# MCU.net
KiCad netlist of a schematic drawn in Altium Designer
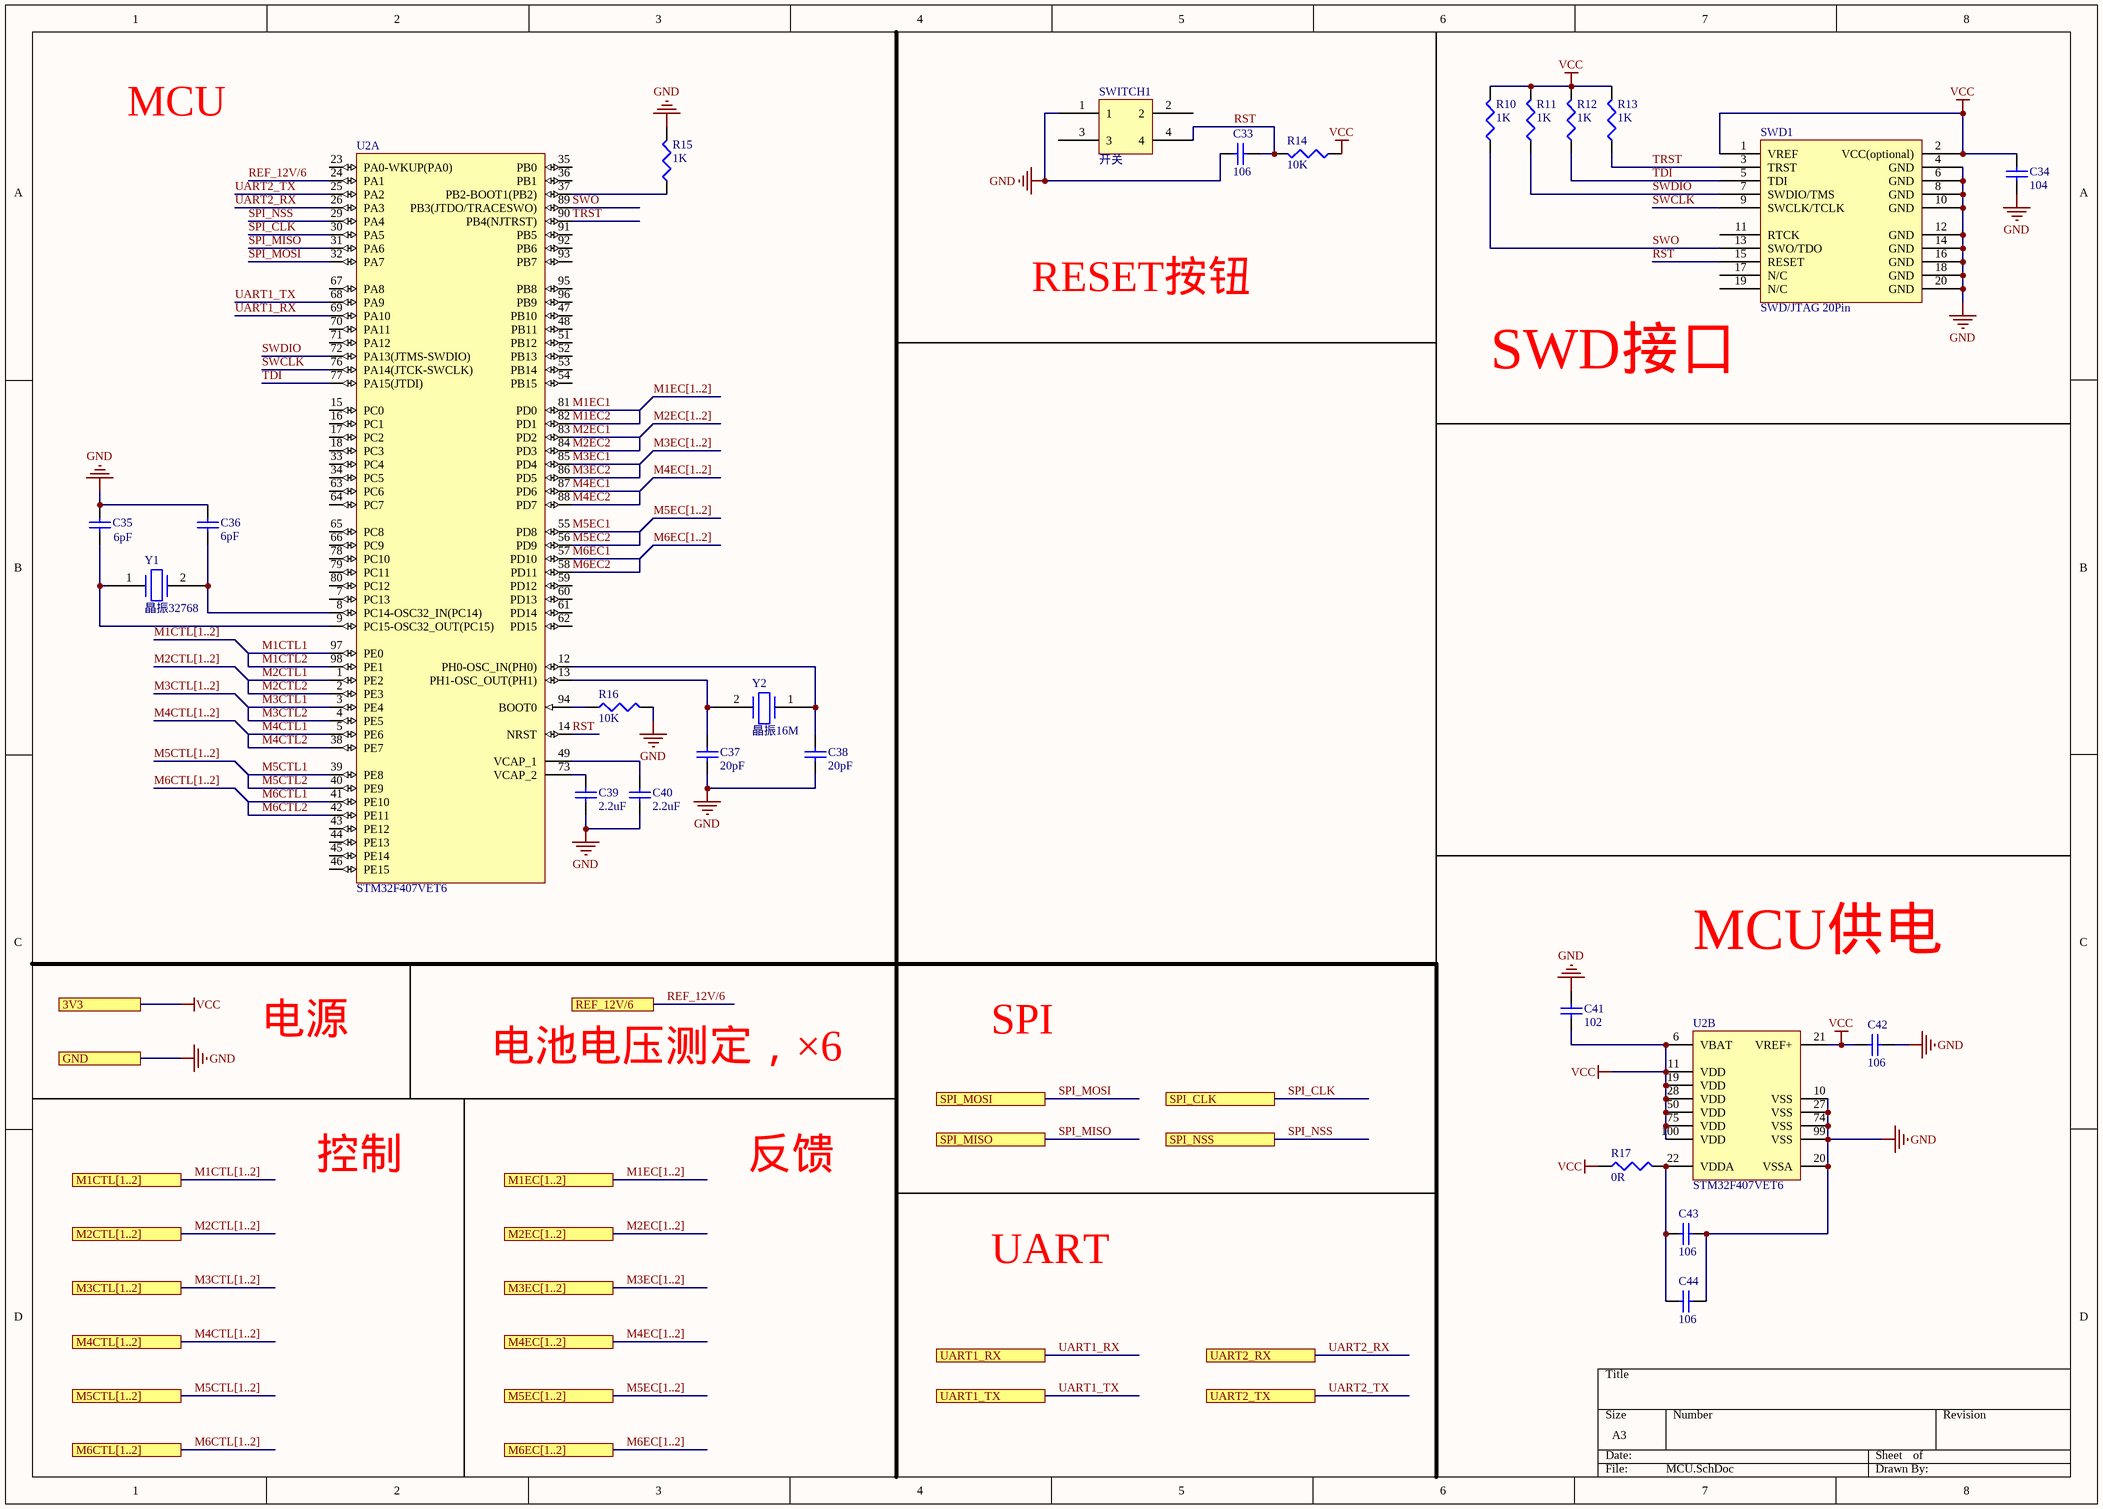
[diagram p0: MCU.SchDoc]

(export (version "E")
  (design (tool "Eeschema 10.0.6"))
  (components
    (comp (ref "C33")
      (value "106")
      (footprint "MY0805")
      (description "Capacitor")
      (fields (field (name "PUBLISHER") "Altium Limited"))
      (libsource (lib "Miscellaneous Devices") (part "Cap"))
    )
    (comp (ref "C34")
      (value "104")
      (footprint "MY0805")
      (description "Capacitor")
      (fields (field (name "PUBLISHER") "Altium Limited"))
      (libsource (lib "Miscellaneous Devices") (part "Cap"))
    )
    (comp (ref "C35")
      (value "6pF")
      (footprint "MY0805")
      (description "Capacitor")
      (fields (field (name "PUBLISHER") "Altium Limited"))
      (libsource (lib "Miscellaneous Devices") (part "Cap"))
    )
    (comp (ref "C36")
      (value "6pF")
      (footprint "MY0805")
      (description "Capacitor")
      (fields (field (name "PUBLISHER") "Altium Limited"))
      (libsource (lib "Miscellaneous Devices") (part "Cap"))
    )
    (comp (ref "C37")
      (value "20pF")
      (footprint "MY0805")
      (description "Capacitor")
      (fields (field (name "PUBLISHER") "Altium Limited"))
      (libsource (lib "Miscellaneous Devices") (part "Cap"))
    )
    (comp (ref "C38")
      (value "20pF")
      (footprint "MY0805")
      (description "Capacitor")
      (fields (field (name "PUBLISHER") "Altium Limited"))
      (libsource (lib "Miscellaneous Devices") (part "Cap"))
    )
    (comp (ref "C39")
      (value "2.2uF")
      (footprint "MY0805")
      (description "Capacitor")
      (fields (field (name "PUBLISHER") "Altium Limited"))
      (libsource (lib "Miscellaneous Devices") (part "Cap"))
    )
    (comp (ref "C40")
      (value "2.2uF")
      (footprint "MY0805")
      (description "Capacitor")
      (fields (field (name "PUBLISHER") "Altium Limited"))
      (libsource (lib "Miscellaneous Devices") (part "Cap"))
    )
    (comp (ref "C41")
      (value "102")
      (footprint "MY0805")
      (description "Capacitor")
      (fields (field (name "PUBLISHER") "Altium Limited"))
      (libsource (lib "Miscellaneous Devices") (part "Cap"))
    )
    (comp (ref "C42")
      (value "106")
      (footprint "MY0805")
      (description "Capacitor")
      (fields (field (name "PUBLISHER") "Altium Limited"))
      (libsource (lib "Miscellaneous Devices") (part "Cap"))
    )
    (comp (ref "C43")
      (value "106")
      (footprint "MY0805")
      (description "Capacitor")
      (fields (field (name "PUBLISHER") "Altium Limited"))
      (libsource (lib "Miscellaneous Devices") (part "Cap"))
    )
    (comp (ref "C44")
      (value "106")
      (footprint "MY0805")
      (description "Capacitor")
      (fields (field (name "PUBLISHER") "Altium Limited"))
      (libsource (lib "Miscellaneous Devices") (part "Cap"))
    )
    (comp (ref "R10")
      (value "1K")
      (footprint "MY0805")
      (description "Resistor")
      (fields (field (name "PUBLISHER") "Altium Limited"))
      (libsource (lib "Miscellaneous Devices") (part "Res3"))
    )
    (comp (ref "R11")
      (value "1K")
      (footprint "MY0805")
      (description "Resistor")
      (fields (field (name "PUBLISHER") "Altium Limited"))
      (libsource (lib "Miscellaneous Devices") (part "Res3"))
    )
    (comp (ref "R12")
      (value "1K")
      (footprint "MY0805")
      (description "Resistor")
      (fields (field (name "PUBLISHER") "Altium Limited"))
      (libsource (lib "Miscellaneous Devices") (part "Res3"))
    )
    (comp (ref "R13")
      (value "1K")
      (footprint "MY0805")
      (description "Resistor")
      (fields (field (name "PUBLISHER") "Altium Limited"))
      (libsource (lib "Miscellaneous Devices") (part "Res3"))
    )
    (comp (ref "R14")
      (value "10K")
      (footprint "MY0805")
      (description "Resistor")
      (fields (field (name "PUBLISHER") "Altium Limited"))
      (libsource (lib "Miscellaneous Devices") (part "Res3"))
    )
    (comp (ref "R15")
      (value "1K")
      (footprint "MY0805")
      (description "Resistor")
      (fields (field (name "PUBLISHER") "Altium Limited"))
      (libsource (lib "Miscellaneous Devices") (part "Res3"))
    )
    (comp (ref "R16")
      (value "10K")
      (footprint "MY0805")
      (description "Resistor")
      (fields (field (name "PUBLISHER") "Altium Limited"))
      (libsource (lib "Miscellaneous Devices") (part "Res3"))
    )
    (comp (ref "R17")
      (value "0R")
      (footprint "MY0805")
      (description "Resistor")
      (fields (field (name "PUBLISHER") "Altium Limited"))
      (libsource (lib "Miscellaneous Devices") (part "Res3"))
    )
    (comp (ref "SWD1")
      (value "SWD/JTAG 20Pin")
      (footprint "SWD 20Pin")
      (libsource (lib "Schlib1") (part "SWD/JTAG 20Pin"))
    )
    (comp (ref "SWITCH1") (value "开关") (footprint "开关") (libsource (lib "Schlib1") (part "开关")))
    (comp (ref "U2")
      (value "STM32F407VET6")
      (footprint "STM-LQFP100_N")
      (fields (field (name "MANUFACTURER") "STMicroelectronics"))
      (libsource (lib "STMicroelectronics STM32 F4") (part "STM32F407VET6"))
    )
    (comp (ref "Y1") (value "晶振32768") (footprint "晶振32768K_AT38") (libsource (lib "Schlib1") (part "晶振")))
    (comp (ref "Y2") (value "晶振16M") (footprint "晶振16M") (libsource (lib "Schlib1") (part "晶振")))
  )
  (nets
    (net (code "1") (name "/M1CTL1") (class "Default")
      (node (ref "U2") (pin "97") (pinfunction "PE0_97") (pintype "bidirectional"))
    )
    (net (code "2") (name "/M1CTL2") (class "Default")
      (node (ref "U2") (pin "98") (pinfunction "PE1_98") (pintype "bidirectional"))
    )
    (net (code "4") (name "/M1EC1") (class "Default")
      (node (ref "U2") (pin "81") (pinfunction "PD0_81") (pintype "bidirectional"))
    )
    (net (code "5") (name "/M1EC2") (class "Default")
      (node (ref "U2") (pin "82") (pinfunction "PD1_82") (pintype "bidirectional"))
    )
    (net (code "7") (name "/M2CTL1") (class "Default")
      (node (ref "U2") (pin "1") (pinfunction "PE2_1") (pintype "bidirectional"))
    )
    (net (code "8") (name "/M2CTL2") (class "Default")
      (node (ref "U2") (pin "2") (pinfunction "PE3_2") (pintype "bidirectional"))
    )
    (net (code "10") (name "/M2EC1") (class "Default")
      (node (ref "U2") (pin "83") (pinfunction "PD2_83") (pintype "bidirectional"))
    )
    (net (code "11") (name "/M2EC2") (class "Default")
      (node (ref "U2") (pin "84") (pinfunction "PD3_84") (pintype "bidirectional"))
    )
    (net (code "13") (name "/M3CTL1") (class "Default")
      (node (ref "U2") (pin "3") (pinfunction "PE4_3") (pintype "bidirectional"))
    )
    (net (code "14") (name "/M3CTL2") (class "Default")
      (node (ref "U2") (pin "4") (pinfunction "PE5_4") (pintype "bidirectional"))
    )
    (net (code "16") (name "/M3EC1") (class "Default")
      (node (ref "U2") (pin "85") (pinfunction "PD4_85") (pintype "bidirectional"))
    )
    (net (code "17") (name "/M3EC2") (class "Default")
      (node (ref "U2") (pin "86") (pinfunction "PD5_86") (pintype "bidirectional"))
    )
    (net (code "19") (name "/M4CTL1") (class "Default")
      (node (ref "U2") (pin "5") (pinfunction "PE6_5") (pintype "bidirectional"))
    )
    (net (code "20") (name "/M4CTL2") (class "Default")
      (node (ref "U2") (pin "38") (pinfunction "PE7_38") (pintype "bidirectional"))
    )
    (net (code "22") (name "/M4EC1") (class "Default")
      (node (ref "U2") (pin "87") (pinfunction "PD6_87") (pintype "bidirectional"))
    )
    (net (code "23") (name "/M4EC2") (class "Default")
      (node (ref "U2") (pin "88") (pinfunction "PD7_88") (pintype "bidirectional"))
    )
    (net (code "25") (name "/M5CTL1") (class "Default")
      (node (ref "U2") (pin "39") (pinfunction "PE8_39") (pintype "bidirectional"))
    )
    (net (code "26") (name "/M5CTL2") (class "Default")
      (node (ref "U2") (pin "40") (pinfunction "PE9_40") (pintype "bidirectional"))
    )
    (net (code "28") (name "/M5EC1") (class "Default")
      (node (ref "U2") (pin "55") (pinfunction "PD8_55") (pintype "bidirectional"))
    )
    (net (code "29") (name "/M5EC2") (class "Default")
      (node (ref "U2") (pin "56") (pinfunction "PD9_56") (pintype "bidirectional"))
    )
    (net (code "31") (name "/M6CTL1") (class "Default")
      (node (ref "U2") (pin "41") (pinfunction "PE10_41") (pintype "bidirectional"))
    )
    (net (code "32") (name "/M6CTL2") (class "Default")
      (node (ref "U2") (pin "42") (pinfunction "PE11_42") (pintype "bidirectional"))
    )
    (net (code "34") (name "/M6EC1") (class "Default")
      (node (ref "U2") (pin "57") (pinfunction "PD10_57") (pintype "bidirectional"))
    )
    (net (code "35") (name "/M6EC2") (class "Default")
      (node (ref "U2") (pin "58") (pinfunction "PD11_58") (pintype "bidirectional"))
    )
    (net (code "37") (name "/REF_12V{slash}6") (class "Default")
      (node (ref "U2") (pin "24") (pinfunction "PA1_24") (pintype "bidirectional"))
    )
    (net (code "38") (name "/RST") (class "Default")
      (node (ref "C33") (pin "2") (pinfunction "2_2") (pintype "passive"))
      (node (ref "R14") (pin "2") (pinfunction "2_2") (pintype "passive"))
      (node (ref "SWD1") (pin "15") (pinfunction "RESET_15") (pintype "passive"))
      (node (ref "SWITCH1") (pin "4") (pinfunction "4_4") (pintype "passive"))
      (node (ref "U2") (pin "14") (pinfunction "NRST_14") (pintype "bidirectional"))
    )
    (net (code "39") (name "/SPI_CLK") (class "Default")
      (node (ref "U2") (pin "30") (pinfunction "PA5_30") (pintype "bidirectional"))
    )
    (net (code "40") (name "/SPI_MISO") (class "Default")
      (node (ref "U2") (pin "31") (pinfunction "PA6_31") (pintype "bidirectional"))
    )
    (net (code "41") (name "/SPI_MOSI") (class "Default")
      (node (ref "U2") (pin "32") (pinfunction "PA7_32") (pintype "bidirectional"))
    )
    (net (code "42") (name "/SPI_NSS") (class "Default")
      (node (ref "U2") (pin "29") (pinfunction "PA4_29") (pintype "bidirectional"))
    )
    (net (code "43") (name "/SWCLK") (class "Default")
      (node (ref "SWD1") (pin "9") (pinfunction "SWCLK/TCLK_9") (pintype "passive"))
      (node (ref "U2") (pin "76") (pinfunction "PA14(JTCK-SWCLK)_76") (pintype "bidirectional"))
    )
    (net (code "44") (name "/SWDIO") (class "Default")
      (node (ref "R11") (pin "1") (pinfunction "1_1") (pintype "passive"))
      (node (ref "SWD1") (pin "7") (pinfunction "SWDIO/TMS_7") (pintype "passive"))
      (node (ref "U2") (pin "72") (pinfunction "PA13(JTMS-SWDIO)_72") (pintype "bidirectional"))
    )
    (net (code "45") (name "/SWO") (class "Default")
      (node (ref "R10") (pin "1") (pinfunction "1_1") (pintype "passive"))
      (node (ref "SWD1") (pin "13") (pinfunction "SWO/TDO_13") (pintype "passive"))
      (node (ref "U2") (pin "89") (pinfunction "PB3(JTDO/TRACESWO)_89") (pintype "bidirectional"))
    )
    (net (code "46") (name "/TDI") (class "Default")
      (node (ref "R12") (pin "1") (pinfunction "1_1") (pintype "passive"))
      (node (ref "SWD1") (pin "5") (pinfunction "TDI_5") (pintype "passive"))
      (node (ref "U2") (pin "77") (pinfunction "PA15(JTDI)_77") (pintype "bidirectional"))
    )
    (net (code "47") (name "/TRST") (class "Default")
      (node (ref "R13") (pin "1") (pinfunction "1_1") (pintype "passive"))
      (node (ref "SWD1") (pin "3") (pinfunction "TRST_3") (pintype "passive"))
      (node (ref "U2") (pin "90") (pinfunction "PB4(NJTRST)_90") (pintype "bidirectional"))
    )
    (net (code "48") (name "/UART1_RX") (class "Default")
      (node (ref "U2") (pin "69") (pinfunction "PA10_69") (pintype "bidirectional"))
    )
    (net (code "49") (name "/UART1_TX") (class "Default")
      (node (ref "U2") (pin "68") (pinfunction "PA9_68") (pintype "bidirectional"))
    )
    (net (code "50") (name "/UART2_RX") (class "Default")
      (node (ref "U2") (pin "26") (pinfunction "PA3_26") (pintype "bidirectional"))
    )
    (net (code "51") (name "/UART2_TX") (class "Default")
      (node (ref "U2") (pin "25") (pinfunction "PA2_25") (pintype "bidirectional"))
    )
    (net (code "52") (name "GND") (class "Default")
      (node (ref "C33") (pin "1") (pinfunction "1_1") (pintype "passive"))
      (node (ref "C34") (pin "1") (pinfunction "1_1") (pintype "passive"))
      (node (ref "C35") (pin "2") (pinfunction "2_2") (pintype "passive"))
      (node (ref "C36") (pin "2") (pinfunction "2_2") (pintype "passive"))
      (node (ref "C37") (pin "2") (pinfunction "2_2") (pintype "passive"))
      (node (ref "C38") (pin "2") (pinfunction "2_2") (pintype "passive"))
      (node (ref "C39") (pin "1") (pinfunction "1_1") (pintype "passive"))
      (node (ref "C40") (pin "1") (pinfunction "1_1") (pintype "passive"))
      (node (ref "C41") (pin "1") (pinfunction "1_1") (pintype "passive"))
      (node (ref "C42") (pin "2") (pinfunction "2_2") (pintype "passive"))
      (node (ref "C43") (pin "2") (pinfunction "2_2") (pintype "passive"))
      (node (ref "C44") (pin "2") (pinfunction "2_2") (pintype "passive"))
      (node (ref "R15") (pin "2") (pinfunction "2_2") (pintype "passive"))
      (node (ref "R16") (pin "2") (pinfunction "2_2") (pintype "passive"))
      (node (ref "SWD1") (pin "10") (pinfunction "GND_10") (pintype "passive"))
      (node (ref "SWD1") (pin "12") (pinfunction "GND_12") (pintype "passive"))
      (node (ref "SWD1") (pin "14") (pinfunction "GND_14") (pintype "passive"))
      (node (ref "SWD1") (pin "16") (pinfunction "GND_16") (pintype "passive"))
      (node (ref "SWD1") (pin "18") (pinfunction "GND_18") (pintype "passive"))
      (node (ref "SWD1") (pin "20") (pinfunction "GND_20") (pintype "passive"))
      (node (ref "SWD1") (pin "4") (pinfunction "GND_4") (pintype "passive"))
      (node (ref "SWD1") (pin "6") (pinfunction "GND_6") (pintype "passive"))
      (node (ref "SWD1") (pin "8") (pinfunction "GND_8") (pintype "passive"))
      (node (ref "SWITCH1") (pin "1") (pinfunction "1_1") (pintype "passive"))
      (node (ref "U2") (pin "10") (pinfunction "VSS_10") (pintype "power_in"))
      (node (ref "U2") (pin "20") (pinfunction "VSSA_20") (pintype "power_in"))
      (node (ref "U2") (pin "27") (pinfunction "VSS_27") (pintype "power_in"))
      (node (ref "U2") (pin "74") (pinfunction "VSS_74") (pintype "power_in"))
      (node (ref "U2") (pin "99") (pinfunction "VSS_99") (pintype "power_in"))
    )
    (net (code "53") (name "Net-(U2A-BOOT0)") (class "Default")
      (node (ref "R16") (pin "1") (pinfunction "1_1") (pintype "passive"))
      (node (ref "U2") (pin "94") (pinfunction "BOOT0_94") (pintype "input"))
    )
    (net (code "54") (name "Net-(U2A-PB2-BOOT1(PB2))") (class "Default")
      (node (ref "R15") (pin "1") (pinfunction "1_1") (pintype "passive"))
      (node (ref "U2") (pin "37") (pinfunction "PB2-BOOT1(PB2)_37") (pintype "bidirectional"))
    )
    (net (code "55") (name "Net-(U2A-PC14-OSC32_IN(PC14))") (class "Default")
      (node (ref "C36") (pin "1") (pinfunction "1_1") (pintype "passive"))
      (node (ref "U2") (pin "8") (pinfunction "PC14-OSC32_IN(PC14)_8") (pintype "bidirectional"))
      (node (ref "Y1") (pin "2") (pinfunction "2_2") (pintype "passive"))
    )
    (net (code "56") (name "Net-(U2A-PC15-OSC32_OUT(PC15))") (class "Default")
      (node (ref "C35") (pin "1") (pinfunction "1_1") (pintype "passive"))
      (node (ref "U2") (pin "9") (pinfunction "PC15-OSC32_OUT(PC15)_9") (pintype "bidirectional"))
      (node (ref "Y1") (pin "1") (pinfunction "1_1") (pintype "passive"))
    )
    (net (code "57") (name "Net-(U2A-PH0-OSC_IN(PH0))") (class "Default")
      (node (ref "C38") (pin "1") (pinfunction "1_1") (pintype "passive"))
      (node (ref "U2") (pin "12") (pinfunction "PH0-OSC_IN(PH0)_12") (pintype "bidirectional"))
      (node (ref "Y2") (pin "1") (pinfunction "1_1") (pintype "passive"))
    )
    (net (code "58") (name "Net-(U2A-PH1-OSC_OUT(PH1))") (class "Default")
      (node (ref "C37") (pin "1") (pinfunction "1_1") (pintype "passive"))
      (node (ref "U2") (pin "13") (pinfunction "PH1-OSC_OUT(PH1)_13") (pintype "bidirectional"))
      (node (ref "Y2") (pin "2") (pinfunction "2_2") (pintype "passive"))
    )
    (net (code "59") (name "Net-(U2A-VCAP_1)") (class "Default")
      (node (ref "C40") (pin "2") (pinfunction "2_2") (pintype "passive"))
      (node (ref "U2") (pin "49") (pinfunction "VCAP_1_49") (pintype "power_in"))
    )
    (net (code "60") (name "Net-(U2A-VCAP_2)") (class "Default")
      (node (ref "C39") (pin "2") (pinfunction "2_2") (pintype "passive"))
      (node (ref "U2") (pin "73") (pinfunction "VCAP_2_73") (pintype "power_in"))
    )
    (net (code "61") (name "Net-(U2B-VDDA)") (class "Default")
      (node (ref "C43") (pin "1") (pinfunction "1_1") (pintype "passive"))
      (node (ref "C44") (pin "1") (pinfunction "1_1") (pintype "passive"))
      (node (ref "R17") (pin "2") (pinfunction "2_2") (pintype "passive"))
      (node (ref "U2") (pin "22") (pinfunction "VDDA_22") (pintype "power_in"))
    )
    (net (code "62") (name "VCC") (class "Default")
      (node (ref "C34") (pin "2") (pinfunction "2_2") (pintype "passive"))
      (node (ref "C41") (pin "2") (pinfunction "2_2") (pintype "passive"))
      (node (ref "C42") (pin "1") (pinfunction "1_1") (pintype "passive"))
      (node (ref "R10") (pin "2") (pinfunction "2_2") (pintype "passive"))
      (node (ref "R11") (pin "2") (pinfunction "2_2") (pintype "passive"))
      (node (ref "R12") (pin "2") (pinfunction "2_2") (pintype "passive"))
      (node (ref "R13") (pin "2") (pinfunction "2_2") (pintype "passive"))
      (node (ref "R14") (pin "1") (pinfunction "1_1") (pintype "passive"))
      (node (ref "R17") (pin "1") (pinfunction "1_1") (pintype "passive"))
      (node (ref "SWD1") (pin "1") (pinfunction "VREF_1") (pintype "passive"))
      (node (ref "SWD1") (pin "2") (pinfunction "VCC(optional)_2") (pintype "passive"))
      (node (ref "U2") (pin "100") (pinfunction "VDD_100") (pintype "power_in"))
      (node (ref "U2") (pin "11") (pinfunction "VDD_11") (pintype "power_in"))
      (node (ref "U2") (pin "19") (pinfunction "VDD_19") (pintype "power_in"))
      (node (ref "U2") (pin "21") (pinfunction "VREF+_21") (pintype "power_in"))
      (node (ref "U2") (pin "28") (pinfunction "VDD_28") (pintype "power_in"))
      (node (ref "U2") (pin "50") (pinfunction "VDD_50") (pintype "power_in"))
      (node (ref "U2") (pin "6") (pinfunction "VBAT_6") (pintype "power_in"))
      (node (ref "U2") (pin "75") (pinfunction "VDD_75") (pintype "power_in"))
    )
    (net (code "63") (name "unconnected-(SWD1-N{slash}C-Pad17)") (class "Default")
      (node (ref "SWD1") (pin "17") (pinfunction "N/C_17") (pintype "passive"))
    )
    (net (code "64") (name "unconnected-(SWD1-N{slash}C-Pad19)") (class "Default")
      (node (ref "SWD1") (pin "19") (pinfunction "N/C_19") (pintype "passive"))
    )
    (net (code "65") (name "unconnected-(SWD1-RTCK-Pad11)") (class "Default")
      (node (ref "SWD1") (pin "11") (pinfunction "RTCK_11") (pintype "passive"))
    )
    (net (code "66") (name "unconnected-(SWITCH1-Pad2)") (class "Default")
      (node (ref "SWITCH1") (pin "2") (pinfunction "2_2") (pintype "passive"))
    )
    (net (code "67") (name "unconnected-(SWITCH1-Pad3)") (class "Default")
      (node (ref "SWITCH1") (pin "3") (pinfunction "3_3") (pintype "passive"))
    )
    (net (code "68") (name "unconnected-(U2A-PA0-WKUP(PA0)-Pad23)") (class "Default")
      (node (ref "U2") (pin "23") (pinfunction "PA0-WKUP(PA0)_23") (pintype "bidirectional"))
    )
    (net (code "69") (name "unconnected-(U2A-PA8-Pad67)") (class "Default")
      (node (ref "U2") (pin "67") (pinfunction "PA8_67") (pintype "bidirectional"))
    )
    (net (code "70") (name "unconnected-(U2A-PA11-Pad70)") (class "Default")
      (node (ref "U2") (pin "70") (pinfunction "PA11_70") (pintype "bidirectional"))
    )
    (net (code "71") (name "unconnected-(U2A-PA12-Pad71)") (class "Default")
      (node (ref "U2") (pin "71") (pinfunction "PA12_71") (pintype "bidirectional"))
    )
    (net (code "72") (name "unconnected-(U2A-PB0-Pad35)") (class "Default")
      (node (ref "U2") (pin "35") (pinfunction "PB0_35") (pintype "bidirectional"))
    )
    (net (code "73") (name "unconnected-(U2A-PB1-Pad36)") (class "Default")
      (node (ref "U2") (pin "36") (pinfunction "PB1_36") (pintype "bidirectional"))
    )
    (net (code "74") (name "unconnected-(U2A-PB5-Pad91)") (class "Default")
      (node (ref "U2") (pin "91") (pinfunction "PB5_91") (pintype "bidirectional"))
    )
    (net (code "75") (name "unconnected-(U2A-PB6-Pad92)") (class "Default")
      (node (ref "U2") (pin "92") (pinfunction "PB6_92") (pintype "bidirectional"))
    )
    (net (code "76") (name "unconnected-(U2A-PB7-Pad93)") (class "Default")
      (node (ref "U2") (pin "93") (pinfunction "PB7_93") (pintype "bidirectional"))
    )
    (net (code "77") (name "unconnected-(U2A-PB8-Pad95)") (class "Default")
      (node (ref "U2") (pin "95") (pinfunction "PB8_95") (pintype "bidirectional"))
    )
    (net (code "78") (name "unconnected-(U2A-PB9-Pad96)") (class "Default")
      (node (ref "U2") (pin "96") (pinfunction "PB9_96") (pintype "bidirectional"))
    )
    (net (code "79") (name "unconnected-(U2A-PB10-Pad47)") (class "Default")
      (node (ref "U2") (pin "47") (pinfunction "PB10_47") (pintype "bidirectional"))
    )
    (net (code "80") (name "unconnected-(U2A-PB11-Pad48)") (class "Default")
      (node (ref "U2") (pin "48") (pinfunction "PB11_48") (pintype "bidirectional"))
    )
    (net (code "81") (name "unconnected-(U2A-PB12-Pad51)") (class "Default")
      (node (ref "U2") (pin "51") (pinfunction "PB12_51") (pintype "bidirectional"))
    )
    (net (code "82") (name "unconnected-(U2A-PB13-Pad52)") (class "Default")
      (node (ref "U2") (pin "52") (pinfunction "PB13_52") (pintype "bidirectional"))
    )
    (net (code "83") (name "unconnected-(U2A-PB14-Pad53)") (class "Default")
      (node (ref "U2") (pin "53") (pinfunction "PB14_53") (pintype "bidirectional"))
    )
    (net (code "84") (name "unconnected-(U2A-PB15-Pad54)") (class "Default")
      (node (ref "U2") (pin "54") (pinfunction "PB15_54") (pintype "bidirectional"))
    )
    (net (code "85") (name "unconnected-(U2A-PC0-Pad15)") (class "Default")
      (node (ref "U2") (pin "15") (pinfunction "PC0_15") (pintype "bidirectional"))
    )
    (net (code "86") (name "unconnected-(U2A-PC1-Pad16)") (class "Default")
      (node (ref "U2") (pin "16") (pinfunction "PC1_16") (pintype "bidirectional"))
    )
    (net (code "87") (name "unconnected-(U2A-PC2-Pad17)") (class "Default")
      (node (ref "U2") (pin "17") (pinfunction "PC2_17") (pintype "bidirectional"))
    )
    (net (code "88") (name "unconnected-(U2A-PC3-Pad18)") (class "Default")
      (node (ref "U2") (pin "18") (pinfunction "PC3_18") (pintype "bidirectional"))
    )
    (net (code "89") (name "unconnected-(U2A-PC4-Pad33)") (class "Default")
      (node (ref "U2") (pin "33") (pinfunction "PC4_33") (pintype "bidirectional"))
    )
    (net (code "90") (name "unconnected-(U2A-PC5-Pad34)") (class "Default")
      (node (ref "U2") (pin "34") (pinfunction "PC5_34") (pintype "bidirectional"))
    )
    (net (code "91") (name "unconnected-(U2A-PC6-Pad63)") (class "Default")
      (node (ref "U2") (pin "63") (pinfunction "PC6_63") (pintype "bidirectional"))
    )
    (net (code "92") (name "unconnected-(U2A-PC7-Pad64)") (class "Default")
      (node (ref "U2") (pin "64") (pinfunction "PC7_64") (pintype "bidirectional"))
    )
    (net (code "93") (name "unconnected-(U2A-PC8-Pad65)") (class "Default")
      (node (ref "U2") (pin "65") (pinfunction "PC8_65") (pintype "bidirectional"))
    )
    (net (code "94") (name "unconnected-(U2A-PC9-Pad66)") (class "Default")
      (node (ref "U2") (pin "66") (pinfunction "PC9_66") (pintype "bidirectional"))
    )
    (net (code "95") (name "unconnected-(U2A-PC10-Pad78)") (class "Default")
      (node (ref "U2") (pin "78") (pinfunction "PC10_78") (pintype "bidirectional"))
    )
    (net (code "96") (name "unconnected-(U2A-PC11-Pad79)") (class "Default")
      (node (ref "U2") (pin "79") (pinfunction "PC11_79") (pintype "bidirectional"))
    )
    (net (code "97") (name "unconnected-(U2A-PC12-Pad80)") (class "Default")
      (node (ref "U2") (pin "80") (pinfunction "PC12_80") (pintype "bidirectional"))
    )
    (net (code "98") (name "unconnected-(U2A-PC13-Pad7)") (class "Default")
      (node (ref "U2") (pin "7") (pinfunction "PC13_7") (pintype "bidirectional"))
    )
    (net (code "99") (name "unconnected-(U2A-PD12-Pad59)") (class "Default")
      (node (ref "U2") (pin "59") (pinfunction "PD12_59") (pintype "bidirectional"))
    )
    (net (code "100") (name "unconnected-(U2A-PD13-Pad60)") (class "Default")
      (node (ref "U2") (pin "60") (pinfunction "PD13_60") (pintype "bidirectional"))
    )
    (net (code "101") (name "unconnected-(U2A-PD14-Pad61)") (class "Default")
      (node (ref "U2") (pin "61") (pinfunction "PD14_61") (pintype "bidirectional"))
    )
    (net (code "102") (name "unconnected-(U2A-PD15-Pad62)") (class "Default")
      (node (ref "U2") (pin "62") (pinfunction "PD15_62") (pintype "bidirectional"))
    )
    (net (code "103") (name "unconnected-(U2A-PE12-Pad43)") (class "Default")
      (node (ref "U2") (pin "43") (pinfunction "PE12_43") (pintype "bidirectional"))
    )
    (net (code "104") (name "unconnected-(U2A-PE13-Pad44)") (class "Default")
      (node (ref "U2") (pin "44") (pinfunction "PE13_44") (pintype "bidirectional"))
    )
    (net (code "105") (name "unconnected-(U2A-PE14-Pad45)") (class "Default")
      (node (ref "U2") (pin "45") (pinfunction "PE14_45") (pintype "bidirectional"))
    )
    (net (code "106") (name "unconnected-(U2A-PE15-Pad46)") (class "Default")
      (node (ref "U2") (pin "46") (pinfunction "PE15_46") (pintype "bidirectional"))
    )
  )
)
